# Steuerungsmodul.net
KiCad netlist of a schematic drawn in EAGLE
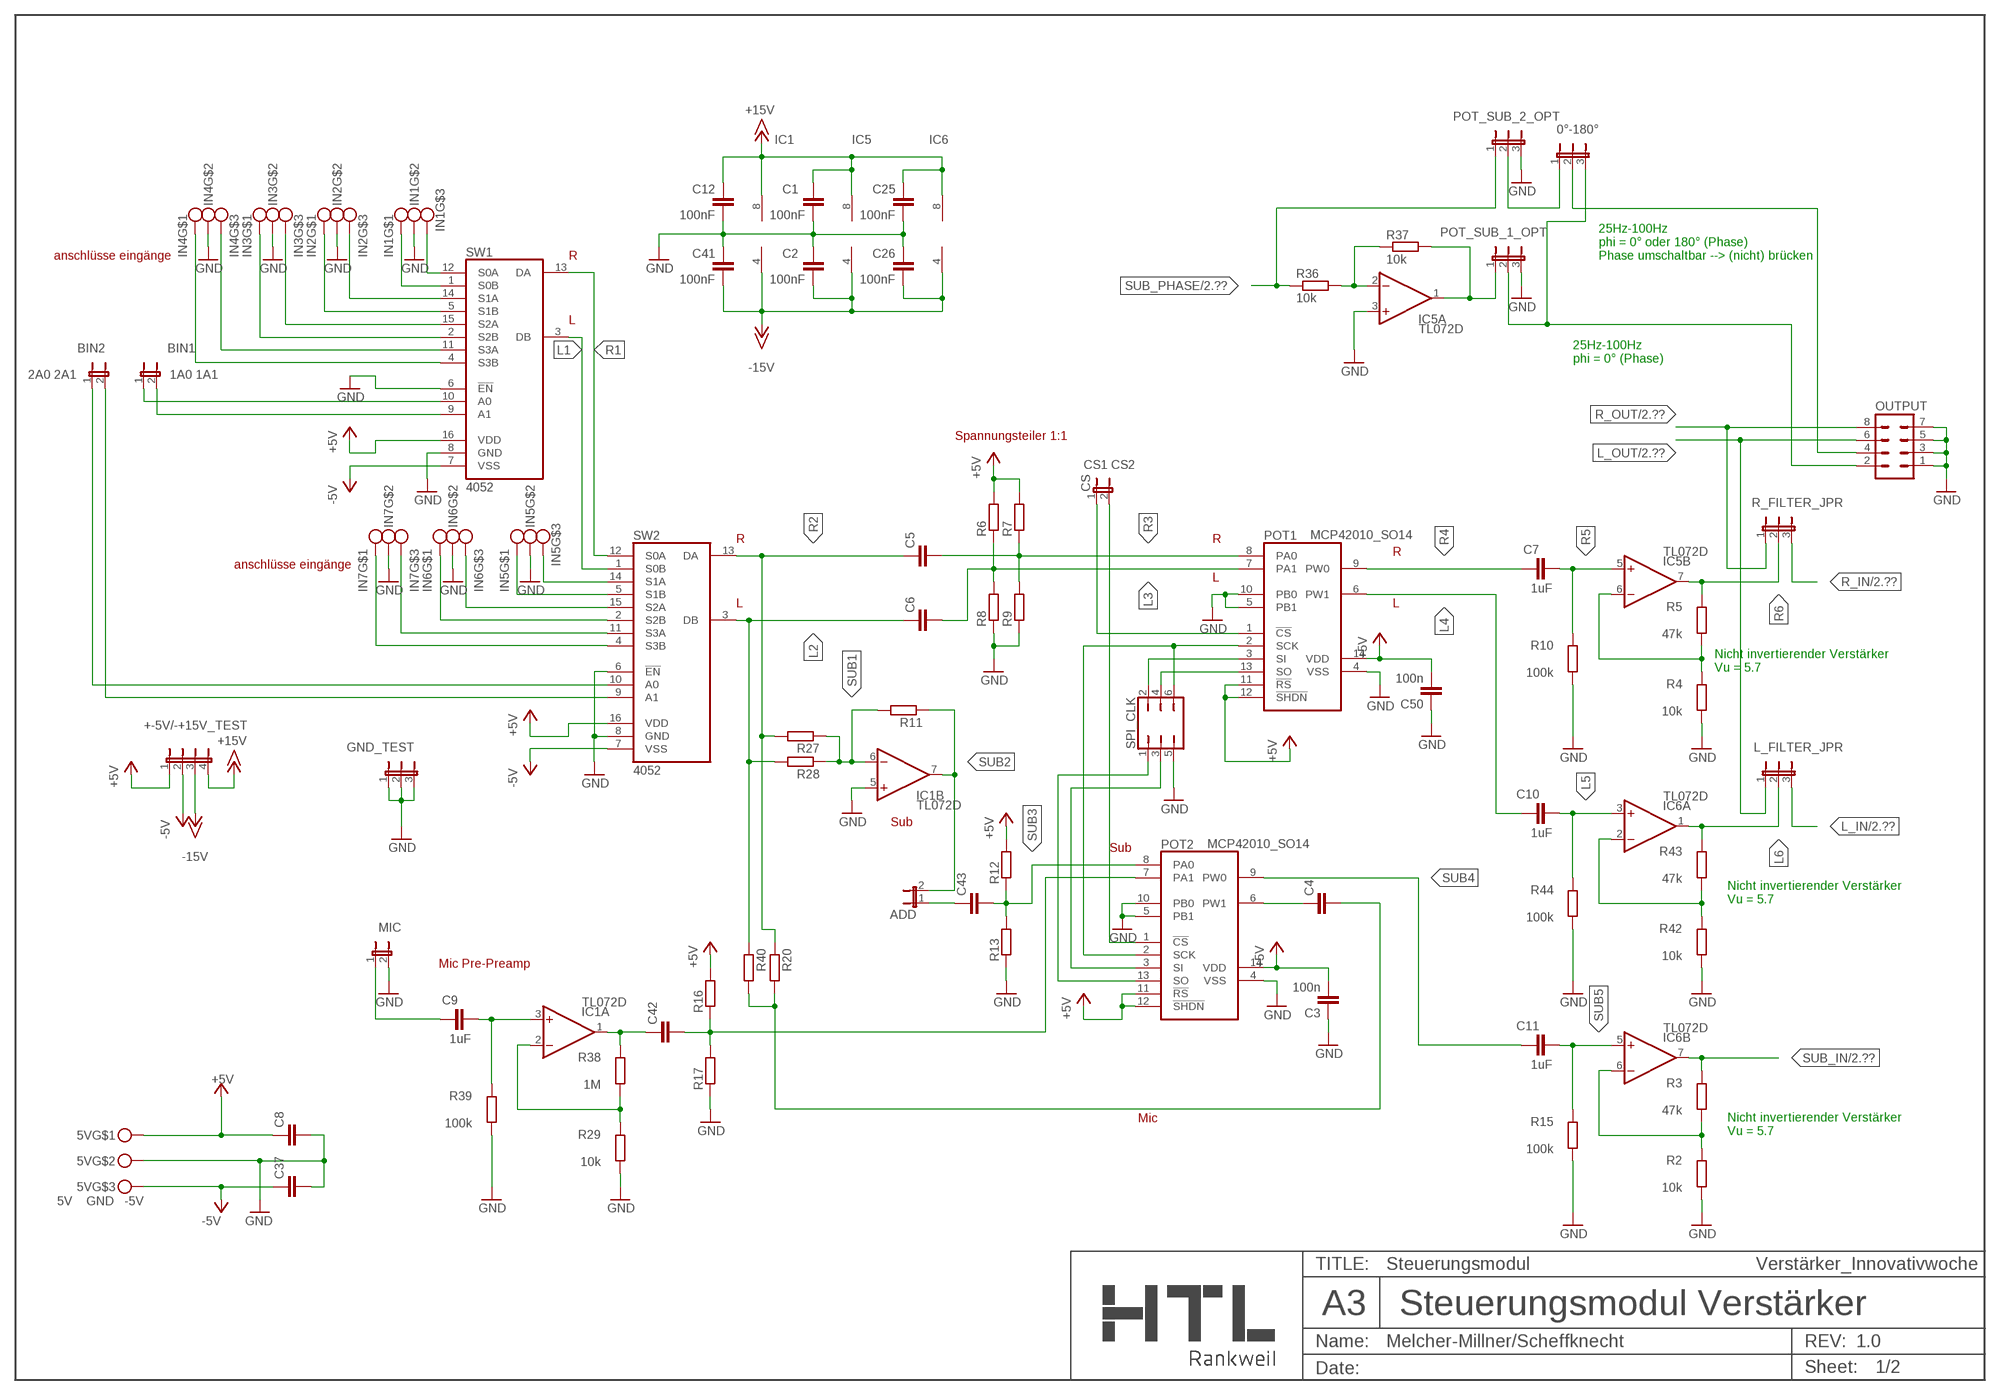
[diagram p0: schematic, sheet 1]
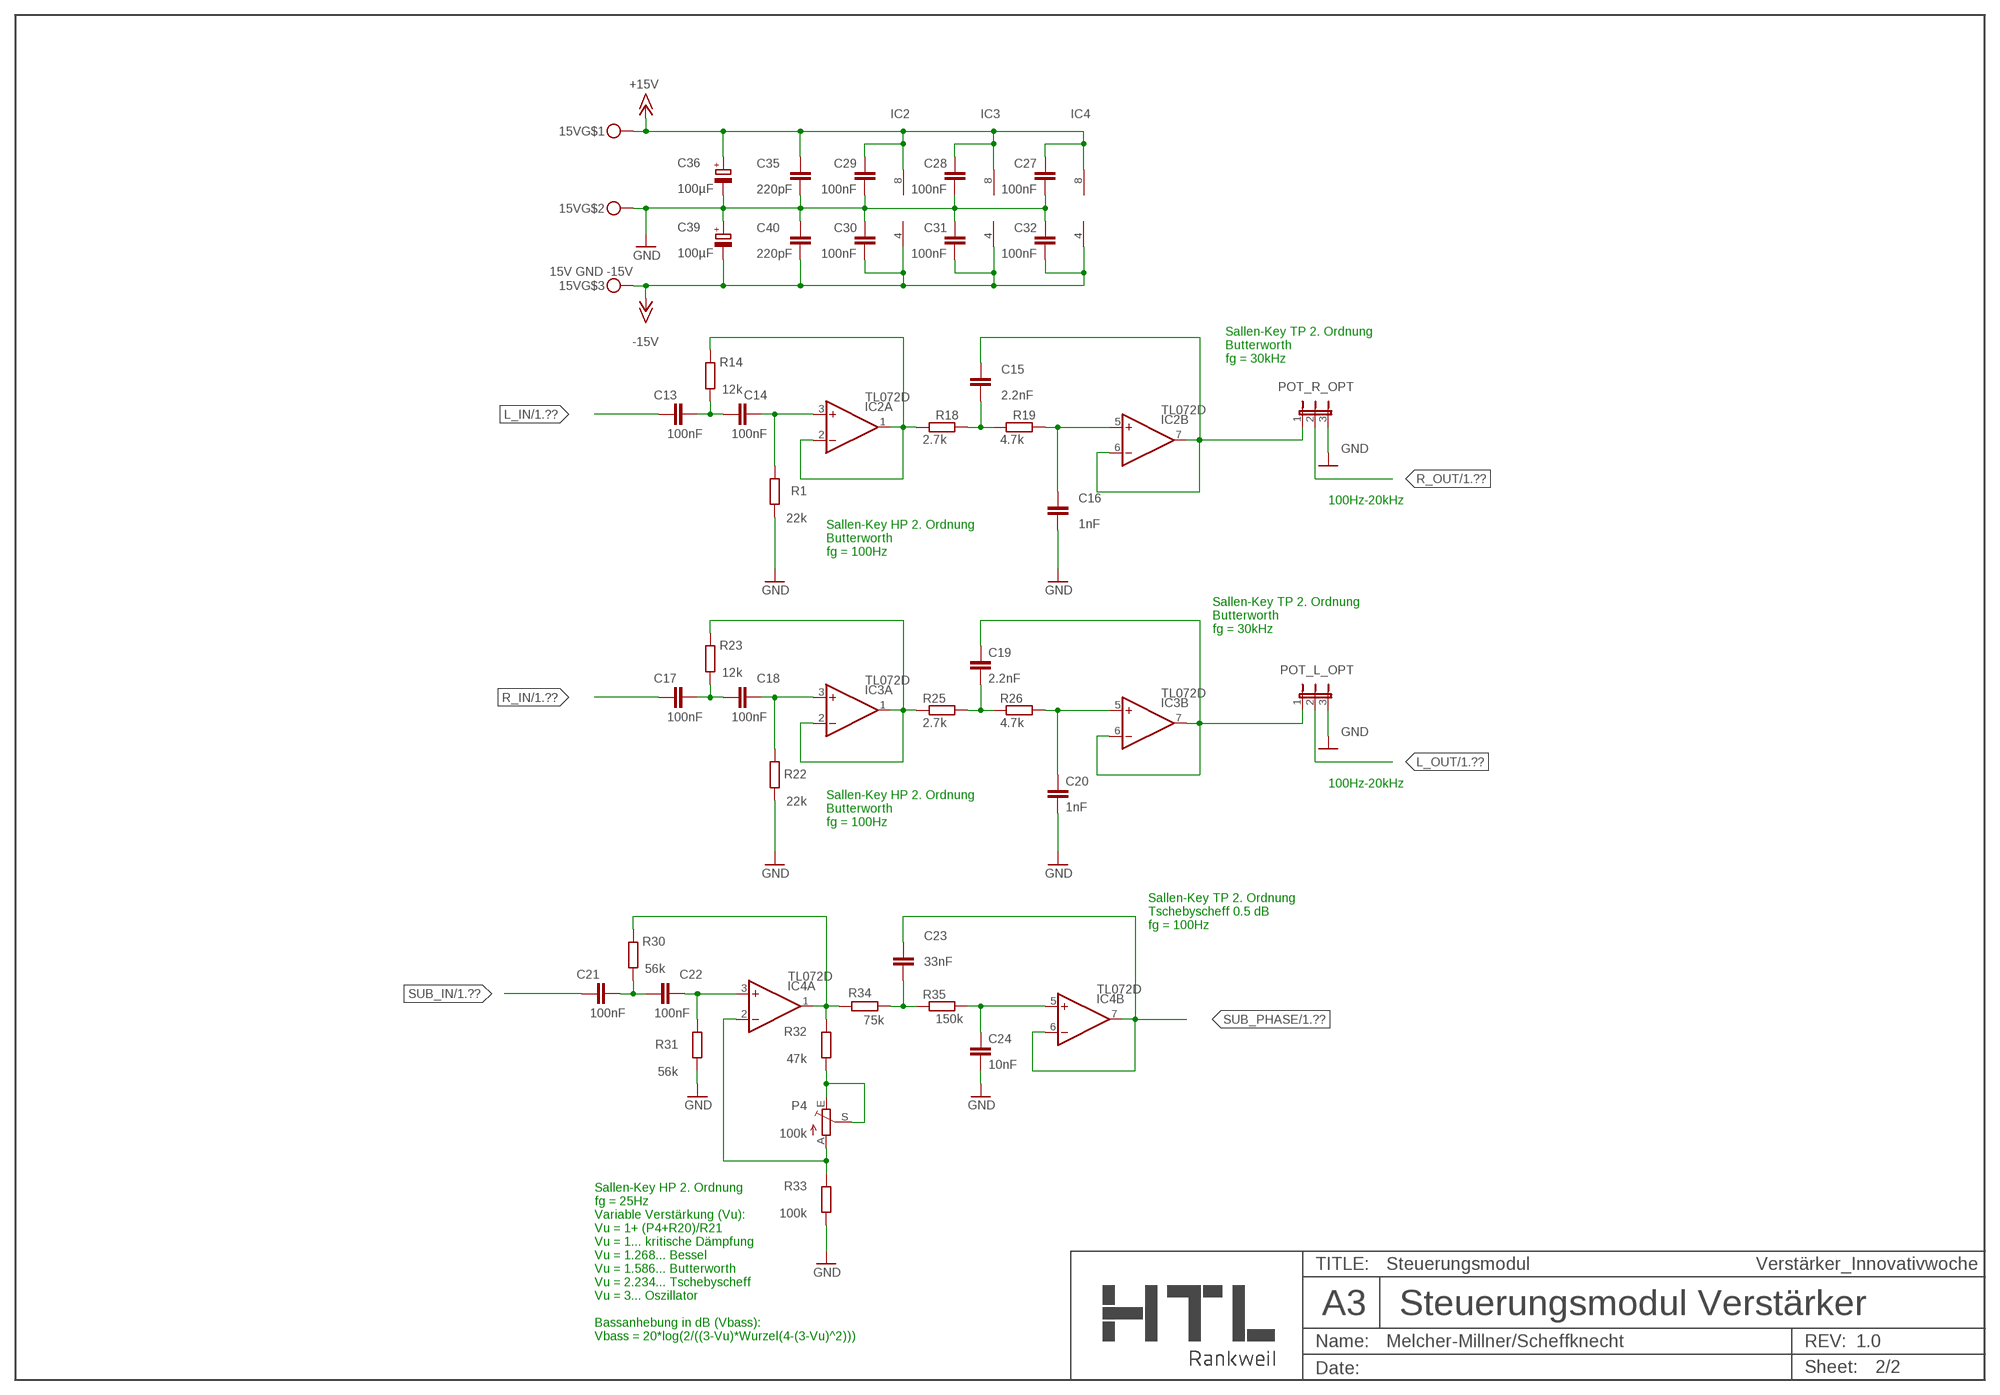
[diagram p1: schematic, sheet 2]

(export (version "E")
  (design (tool "Eeschema 10.0.6"))
  (components
    (comp (ref "15V")
      (value "15V GND -15V")
      (footprint "eagle-import:MKDS3_3_5,08")
      (libsource (lib "eagle-import") (part "MKDS3/3_5,08"))
    )
    (comp (ref "C13")
      (value "100nF")
      (footprint "eagle-import:C0805")
      (libsource (lib "eagle-import") (part "C-EUC0805"))
    )
    (comp (ref "C14")
      (value "100nF")
      (footprint "eagle-import:C0805")
      (libsource (lib "eagle-import") (part "C-EUC0805"))
    )
    (comp (ref "C15")
      (value "2.2nF")
      (footprint "eagle-import:C0805")
      (libsource (lib "eagle-import") (part "C-EUC0805"))
    )
    (comp (ref "C16")
      (value "1nF")
      (footprint "eagle-import:C0805")
      (libsource (lib "eagle-import") (part "C-EUC0805"))
    )
    (comp (ref "C17")
      (value "100nF")
      (footprint "eagle-import:C0805")
      (libsource (lib "eagle-import") (part "C-EUC0805"))
    )
    (comp (ref "C18")
      (value "100nF")
      (footprint "eagle-import:C0805")
      (libsource (lib "eagle-import") (part "C-EUC0805"))
    )
    (comp (ref "C19")
      (value "2.2nF")
      (footprint "eagle-import:C0805")
      (libsource (lib "eagle-import") (part "C-EUC0805"))
    )
    (comp (ref "C20")
      (value "1nF")
      (footprint "eagle-import:C0805")
      (libsource (lib "eagle-import") (part "C-EUC0805"))
    )
    (comp (ref "C21")
      (value "100nF")
      (footprint "eagle-import:C0805")
      (libsource (lib "eagle-import") (part "C-EUC0805"))
    )
    (comp (ref "C22")
      (value "100nF")
      (footprint "eagle-import:C0805")
      (libsource (lib "eagle-import") (part "C-EUC0805"))
    )
    (comp (ref "C23")
      (value "33nF")
      (footprint "eagle-import:C0805")
      (libsource (lib "eagle-import") (part "C-EUC0805"))
    )
    (comp (ref "C24")
      (value "10nF")
      (footprint "eagle-import:C0805")
      (libsource (lib "eagle-import") (part "C-EUC0805"))
    )
    (comp (ref "C27")
      (value "100nF")
      (footprint "eagle-import:C0805")
      (libsource (lib "eagle-import") (part "C-EUC0805"))
    )
    (comp (ref "C28")
      (value "100nF")
      (footprint "eagle-import:C0805")
      (libsource (lib "eagle-import") (part "C-EUC0805"))
    )
    (comp (ref "C29")
      (value "100nF")
      (footprint "eagle-import:C0805")
      (libsource (lib "eagle-import") (part "C-EUC0805"))
    )
    (comp (ref "C30")
      (value "100nF")
      (footprint "eagle-import:C0805")
      (libsource (lib "eagle-import") (part "C-EUC0805"))
    )
    (comp (ref "C31")
      (value "100nF")
      (footprint "eagle-import:C0805")
      (libsource (lib "eagle-import") (part "C-EUC0805"))
    )
    (comp (ref "C32")
      (value "100nF")
      (footprint "eagle-import:C0805")
      (libsource (lib "eagle-import") (part "C-EUC0805"))
    )
    (comp (ref "C35")
      (value "220pF")
      (footprint "eagle-import:C0805")
      (libsource (lib "eagle-import") (part "C-EUC0805"))
    )
    (comp (ref "C36")
      (value "100µF")
      (footprint "eagle-import:E2,5-6")
      (libsource (lib "eagle-import") (part "CPOL-EUE2.5-6"))
    )
    (comp (ref "C39")
      (value "100µF")
      (footprint "eagle-import:E2,5-6")
      (libsource (lib "eagle-import") (part "CPOL-EUE2.5-6"))
    )
    (comp (ref "C40")
      (value "220pF")
      (footprint "eagle-import:C0805")
      (libsource (lib "eagle-import") (part "C-EUC0805"))
    )
    (comp (ref "FRAME2")
      (value "HTL-A3-H")
      (footprint "eagle-import:HTL-LEER")
      (libsource (lib "eagle-import") (part "HTL-A3-H"))
    )
    (comp (ref "IC2")
      (value "TL072D")
      (footprint "eagle-import:SO08")
      (libsource (lib "eagle-import") (part "TL072D"))
    )
    (comp (ref "IC3")
      (value "TL072D")
      (footprint "eagle-import:SO08")
      (libsource (lib "eagle-import") (part "TL072D"))
    )
    (comp (ref "IC4")
      (value "TL072D")
      (footprint "eagle-import:SO08")
      (libsource (lib "eagle-import") (part "TL072D"))
    )
    (comp (ref "P4")
      (value "100k")
      (footprint "eagle-import:S64W")
      (libsource (lib "eagle-import") (part "TRIM_EU-S64W"))
    )
    (comp (ref "POT_L_OPT")
      (value "JMP3")
      (footprint "eagle-import:JMP3")
      (libsource (lib "eagle-import") (part "JMP3"))
    )
    (comp (ref "POT_R_OPT")
      (value "JMP3")
      (footprint "eagle-import:JMP3")
      (libsource (lib "eagle-import") (part "JMP3"))
    )
    (comp (ref "R1")
      (value "22k")
      (footprint "eagle-import:M0805")
      (libsource (lib "eagle-import") (part "R-EU_M0805"))
    )
    (comp (ref "R14")
      (value "12k")
      (footprint "eagle-import:M0805")
      (libsource (lib "eagle-import") (part "R-EU_M0805"))
    )
    (comp (ref "R18")
      (value "2.7k")
      (footprint "eagle-import:M0805")
      (libsource (lib "eagle-import") (part "R-EU_M0805"))
    )
    (comp (ref "R19")
      (value "4.7k")
      (footprint "eagle-import:M0805")
      (libsource (lib "eagle-import") (part "R-EU_M0805"))
    )
    (comp (ref "R22")
      (value "22k")
      (footprint "eagle-import:M0805")
      (libsource (lib "eagle-import") (part "R-EU_M0805"))
    )
    (comp (ref "R23")
      (value "12k")
      (footprint "eagle-import:M0805")
      (libsource (lib "eagle-import") (part "R-EU_M0805"))
    )
    (comp (ref "R25")
      (value "2.7k")
      (footprint "eagle-import:M0805")
      (libsource (lib "eagle-import") (part "R-EU_M0805"))
    )
    (comp (ref "R26")
      (value "4.7k")
      (footprint "eagle-import:M0805")
      (libsource (lib "eagle-import") (part "R-EU_M0805"))
    )
    (comp (ref "R30")
      (value "56k")
      (footprint "eagle-import:M0805")
      (libsource (lib "eagle-import") (part "R-EU_M0805"))
    )
    (comp (ref "R31")
      (value "56k")
      (footprint "eagle-import:M0805")
      (libsource (lib "eagle-import") (part "R-EU_M0805"))
    )
    (comp (ref "R32")
      (value "47k")
      (footprint "eagle-import:M0805")
      (libsource (lib "eagle-import") (part "R-EU_M0805"))
    )
    (comp (ref "R33")
      (value "100k")
      (footprint "eagle-import:M0805")
      (libsource (lib "eagle-import") (part "R-EU_M0805"))
    )
    (comp (ref "R34")
      (value "75k")
      (footprint "eagle-import:M0805")
      (libsource (lib "eagle-import") (part "R-EU_M0805"))
    )
    (comp (ref "R35")
      (value "150k")
      (footprint "eagle-import:M0805")
      (libsource (lib "eagle-import") (part "R-EU_M0805"))
    )
    (comp (ref "+-5V/-+15V_TEST")
      (value "JP4E")
      (footprint "eagle-import:JP4")
      (libsource (lib "eagle-import") (part "JP4E"))
    )
    (comp (ref "0°-180°")
      (value "JMP3")
      (footprint "eagle-import:JMP3")
      (libsource (lib "eagle-import") (part "JMP3"))
    )
    (comp (ref "5V")
      (value "5V GND -5V")
      (footprint "eagle-import:MKDS3_3_5,08")
      (libsource (lib "eagle-import") (part "MKDS3/3_5,08"))
    )
    (comp (ref "ADD")
      (value "JMP2")
      (footprint "eagle-import:JMP2")
      (libsource (lib "eagle-import") (part "JMP2"))
    )
    (comp (ref "BIN1")
      (value "1A0 1A1")
      (footprint "eagle-import:JMP2")
      (libsource (lib "eagle-import") (part "JMP2"))
    )
    (comp (ref "BIN2")
      (value "2A0 2A1")
      (footprint "eagle-import:JMP2")
      (fields (field (name "SPICEPREFIX") "B"))
      (libsource (lib "eagle-import") (part "JMP2"))
    )
    (comp (ref "C1")
      (value "100nF")
      (footprint "eagle-import:C0805")
      (libsource (lib "eagle-import") (part "C-EUC0805"))
    )
    (comp (ref "C2")
      (value "100nF")
      (footprint "eagle-import:C0805")
      (libsource (lib "eagle-import") (part "C-EUC0805"))
    )
    (comp (ref "C3")
      (value "100n")
      (footprint "eagle-import:C0805")
      (libsource (lib "eagle-import") (part "C-EUC0805"))
    )
    (comp (ref "C4")
      (value "C-EUC0805")
      (footprint "eagle-import:C0805")
      (libsource (lib "eagle-import") (part "C-EUC0805"))
    )
    (comp (ref "C5")
      (value "C-EUC0805")
      (footprint "eagle-import:C0805")
      (libsource (lib "eagle-import") (part "C-EUC0805"))
    )
    (comp (ref "C6")
      (value "C-EUC0805")
      (footprint "eagle-import:C0805")
      (libsource (lib "eagle-import") (part "C-EUC0805"))
    )
    (comp (ref "C7")
      (value "1uF")
      (footprint "eagle-import:C025-025X050")
      (libsource (lib "eagle-import") (part "resistor_C-EU025-025X050"))
    )
    (comp (ref "C8")
      (value "C-EUC0805")
      (footprint "eagle-import:C0805")
      (libsource (lib "eagle-import") (part "C-EUC0805"))
    )
    (comp (ref "C9")
      (value "1uF")
      (footprint "eagle-import:C025-025X050")
      (libsource (lib "eagle-import") (part "resistor_C-EU025-025X050"))
    )
    (comp (ref "C10")
      (value "1uF")
      (footprint "eagle-import:C025-025X050")
      (libsource (lib "eagle-import") (part "resistor_C-EU025-025X050"))
    )
    (comp (ref "C11")
      (value "1uF")
      (footprint "eagle-import:C025-025X050")
      (libsource (lib "eagle-import") (part "resistor_C-EU025-025X050"))
    )
    (comp (ref "C12")
      (value "100nF")
      (footprint "eagle-import:C0805")
      (libsource (lib "eagle-import") (part "C-EUC0805"))
    )
    (comp (ref "C25")
      (value "100nF")
      (footprint "eagle-import:C0805")
      (libsource (lib "eagle-import") (part "C-EUC0805"))
    )
    (comp (ref "C26")
      (value "100nF")
      (footprint "eagle-import:C0805")
      (libsource (lib "eagle-import") (part "C-EUC0805"))
    )
    (comp (ref "C37")
      (value "C-EUC0805")
      (footprint "eagle-import:C0805")
      (libsource (lib "eagle-import") (part "C-EUC0805"))
    )
    (comp (ref "C41")
      (value "100nF")
      (footprint "eagle-import:C0805")
      (libsource (lib "eagle-import") (part "C-EUC0805"))
    )
    (comp (ref "C42")
      (value "C-EUC0805")
      (footprint "eagle-import:C0805")
      (libsource (lib "eagle-import") (part "C-EUC0805"))
    )
    (comp (ref "C43")
      (value "C-EUC0805")
      (footprint "eagle-import:C0805")
      (libsource (lib "eagle-import") (part "C-EUC0805"))
    )
    (comp (ref "C50")
      (value "100n")
      (footprint "eagle-import:C0805")
      (libsource (lib "eagle-import") (part "C-EUC0805"))
    )
    (comp (ref "CS")
      (value "CS1 CS2")
      (footprint "eagle-import:JMP2")
      (libsource (lib "eagle-import") (part "JMP2"))
    )
    (comp (ref "FRAME1")
      (value "HTL-A3-H")
      (footprint "eagle-import:HTL-LEER")
      (libsource (lib "eagle-import") (part "HTL-A3-H"))
    )
    (comp (ref "GND_TEST")
      (value "JMP3")
      (footprint "eagle-import:JMP3")
      (libsource (lib "eagle-import") (part "JMP3"))
    )
    (comp (ref "IC1")
      (value "TL072D")
      (footprint "eagle-import:SO08")
      (libsource (lib "eagle-import") (part "TL072D"))
    )
    (comp (ref "IC5")
      (value "TL072D")
      (footprint "eagle-import:SO08")
      (libsource (lib "eagle-import") (part "TL072D"))
    )
    (comp (ref "IC6")
      (value "TL072D")
      (footprint "eagle-import:SO08")
      (libsource (lib "eagle-import") (part "TL072D"))
    )
    (comp (ref "IN1")
      (value "MKDS3/3_5,08")
      (footprint "eagle-import:MKDS3_3_5,08")
      (libsource (lib "eagle-import") (part "MKDS3/3_5,08"))
    )
    (comp (ref "IN2")
      (value "MKDS3/3_5,08")
      (footprint "eagle-import:MKDS3_3_5,08")
      (libsource (lib "eagle-import") (part "MKDS3/3_5,08"))
    )
    (comp (ref "IN3")
      (value "MKDS3/3_5,08")
      (footprint "eagle-import:MKDS3_3_5,08")
      (libsource (lib "eagle-import") (part "MKDS3/3_5,08"))
    )
    (comp (ref "IN4")
      (value "MKDS3/3_5,08")
      (footprint "eagle-import:MKDS3_3_5,08")
      (libsource (lib "eagle-import") (part "MKDS3/3_5,08"))
    )
    (comp (ref "IN5")
      (value "MKDS3/3_5,08")
      (footprint "eagle-import:MKDS3_3_5,08")
      (libsource (lib "eagle-import") (part "MKDS3/3_5,08"))
    )
    (comp (ref "IN6")
      (value "MKDS3/3_5,08")
      (footprint "eagle-import:MKDS3_3_5,08")
      (libsource (lib "eagle-import") (part "MKDS3/3_5,08"))
    )
    (comp (ref "IN7")
      (value "MKDS3/3_5,08")
      (footprint "eagle-import:MKDS3_3_5,08")
      (libsource (lib "eagle-import") (part "MKDS3/3_5,08"))
    )
    (comp (ref "L_FILTER_JPR")
      (value "JMP3")
      (footprint "eagle-import:JMP3")
      (libsource (lib "eagle-import") (part "JMP3"))
    )
    (comp (ref "MIC")
      (value "JMP2")
      (footprint "eagle-import:JMP2")
      (libsource (lib "eagle-import") (part "JMP2"))
    )
    (comp (ref "OUTPUT")
      (value "MA04-2")
      (footprint "eagle-import:MA04-2")
      (libsource (lib "eagle-import") (part "MA04-2"))
    )
    (comp (ref "POT1")
      (value "MCP42010_SO14")
      (footprint "eagle-import:SO14")
      (libsource (lib "eagle-import") (part "MCP42010_SO14"))
    )
    (comp (ref "POT2")
      (value "MCP42010_SO14")
      (footprint "eagle-import:SO14")
      (libsource (lib "eagle-import") (part "MCP42010_SO14"))
    )
    (comp (ref "POT_SUB_1_OPT")
      (value "JMP3")
      (footprint "eagle-import:JMP3")
      (libsource (lib "eagle-import") (part "JMP3"))
    )
    (comp (ref "POT_SUB_2_OPT")
      (value "JMP3")
      (footprint "eagle-import:JMP3")
      (libsource (lib "eagle-import") (part "JMP3"))
    )
    (comp (ref "R2")
      (value "10k")
      (footprint "eagle-import:M0805")
      (libsource (lib "eagle-import") (part "R-EU_M0805"))
    )
    (comp (ref "R3")
      (value "47k")
      (footprint "eagle-import:M0805")
      (libsource (lib "eagle-import") (part "R-EU_M0805"))
    )
    (comp (ref "R4")
      (value "10k")
      (footprint "eagle-import:M0805")
      (libsource (lib "eagle-import") (part "R-EU_M0805"))
    )
    (comp (ref "R5")
      (value "47k")
      (footprint "eagle-import:M0805")
      (libsource (lib "eagle-import") (part "R-EU_M0805"))
    )
    (comp (ref "R6")
      (value "R-EU_M0805")
      (footprint "eagle-import:M0805")
      (libsource (lib "eagle-import") (part "R-EU_M0805"))
    )
    (comp (ref "R7")
      (value "R-EU_M0805")
      (footprint "eagle-import:M0805")
      (libsource (lib "eagle-import") (part "R-EU_M0805"))
    )
    (comp (ref "R8")
      (value "R-EU_M0805")
      (footprint "eagle-import:M0805")
      (libsource (lib "eagle-import") (part "R-EU_M0805"))
    )
    (comp (ref "R9")
      (value "R-EU_M0805")
      (footprint "eagle-import:M0805")
      (libsource (lib "eagle-import") (part "R-EU_M0805"))
    )
    (comp (ref "R10")
      (value "100k")
      (footprint "eagle-import:M0805")
      (libsource (lib "eagle-import") (part "R-EU_M0805"))
    )
    (comp (ref "R11")
      (value "R-EU_M0805")
      (footprint "eagle-import:M0805")
      (libsource (lib "eagle-import") (part "R-EU_M0805"))
    )
    (comp (ref "R12")
      (value "R-EU_M0805")
      (footprint "eagle-import:M0805")
      (libsource (lib "eagle-import") (part "R-EU_M0805"))
    )
    (comp (ref "R13")
      (value "R-EU_M0805")
      (footprint "eagle-import:M0805")
      (libsource (lib "eagle-import") (part "R-EU_M0805"))
    )
    (comp (ref "R15")
      (value "100k")
      (footprint "eagle-import:M0805")
      (libsource (lib "eagle-import") (part "R-EU_M0805"))
    )
    (comp (ref "R16")
      (value "R-EU_M0805")
      (footprint "eagle-import:M0805")
      (libsource (lib "eagle-import") (part "R-EU_M0805"))
    )
    (comp (ref "R17")
      (value "R-EU_M0805")
      (footprint "eagle-import:M0805")
      (libsource (lib "eagle-import") (part "R-EU_M0805"))
    )
    (comp (ref "R20")
      (value "R-EU_M0805")
      (footprint "eagle-import:M0805")
      (libsource (lib "eagle-import") (part "R-EU_M0805"))
    )
    (comp (ref "R27")
      (value "R-EU_M0805")
      (footprint "eagle-import:M0805")
      (libsource (lib "eagle-import") (part "R-EU_M0805"))
    )
    (comp (ref "R28")
      (value "R-EU_M0805")
      (footprint "eagle-import:M0805")
      (libsource (lib "eagle-import") (part "R-EU_M0805"))
    )
    (comp (ref "R29")
      (value "10k")
      (footprint "eagle-import:M0805")
      (libsource (lib "eagle-import") (part "R-EU_M0805"))
    )
    (comp (ref "R36")
      (value "10k")
      (footprint "eagle-import:M0805")
      (libsource (lib "eagle-import") (part "R-EU_M0805"))
    )
    (comp (ref "R37")
      (value "10k")
      (footprint "eagle-import:M0805")
      (libsource (lib "eagle-import") (part "R-EU_M0805"))
    )
    (comp (ref "R38")
      (value "1M")
      (footprint "eagle-import:M0805")
      (libsource (lib "eagle-import") (part "R-EU_M0805"))
    )
    (comp (ref "R39")
      (value "100k")
      (footprint "eagle-import:M0805")
      (libsource (lib "eagle-import") (part "R-EU_M0805"))
    )
    (comp (ref "R40")
      (value "R-EU_M0805")
      (footprint "eagle-import:M0805")
      (libsource (lib "eagle-import") (part "R-EU_M0805"))
    )
    (comp (ref "R42")
      (value "10k")
      (footprint "eagle-import:M0805")
      (libsource (lib "eagle-import") (part "R-EU_M0805"))
    )
    (comp (ref "R43")
      (value "47k")
      (footprint "eagle-import:M0805")
      (libsource (lib "eagle-import") (part "R-EU_M0805"))
    )
    (comp (ref "R44")
      (value "100k")
      (footprint "eagle-import:M0805")
      (libsource (lib "eagle-import") (part "R-EU_M0805"))
    )
    (comp (ref "R_FILTER_JPR")
      (value "JMP3")
      (footprint "eagle-import:JMP3")
      (libsource (lib "eagle-import") (part "JMP3"))
    )
    (comp (ref "SPI_CLK")
      (value "JP3Q")
      (footprint "eagle-import:JP3Q")
      (libsource (lib "eagle-import") (part "JP3Q"))
    )
    (comp (ref "SW1")
      (value "4052")
      (footprint "eagle-import:SO-16")
      (libsource (lib "eagle-import") (part "5042_SO16_NEU"))
    )
    (comp (ref "SW2")
      (value "4052")
      (footprint "eagle-import:SO-16")
      (libsource (lib "eagle-import") (part "5042_SO16_NEU"))
    )
  )
  (nets
    (net (code "1") (name "+5V") (class "Default")
      (node (ref "+-5V/-+15V_TEST") (pin "1") (pinfunction "1_1") (pintype "passive"))
      (node (ref "5V") (pin "P$1") (pinfunction "KL_P$1") (pintype "passive"))
      (node (ref "C3") (pin "2") (pinfunction "2_2") (pintype "passive"))
      (node (ref "C50") (pin "2") (pinfunction "2_2") (pintype "passive"))
      (node (ref "C8") (pin "1") (pinfunction "1_1") (pintype "passive"))
      (node (ref "POT1") (pin "11") (pinfunction "~{RS}_11") (pintype "bidirectional"))
      (node (ref "POT1") (pin "12") (pinfunction "~{SHDN}_12") (pintype "bidirectional"))
      (node (ref "POT1") (pin "14") (pinfunction "VDD_14") (pintype "input"))
      (node (ref "POT2") (pin "11") (pinfunction "~{RS}_11") (pintype "bidirectional"))
      (node (ref "POT2") (pin "12") (pinfunction "~{SHDN}_12") (pintype "bidirectional"))
      (node (ref "POT2") (pin "14") (pinfunction "VDD_14") (pintype "input"))
      (node (ref "R12") (pin "2") (pinfunction "2_2") (pintype "passive"))
      (node (ref "R16") (pin "2") (pinfunction "2_2") (pintype "passive"))
      (node (ref "R6") (pin "2") (pinfunction "2_2") (pintype "passive"))
      (node (ref "R7") (pin "2") (pinfunction "2_2") (pintype "passive"))
      (node (ref "SW1") (pin "16") (pinfunction "VDD_16") (pintype "bidirectional"))
      (node (ref "SW2") (pin "16") (pinfunction "VDD_16") (pintype "bidirectional"))
    )
    (net (code "2") (name "+15V") (class "Default")
      (node (ref "+-5V/-+15V_TEST") (pin "4") (pinfunction "4_4") (pintype "passive"))
      (node (ref "15V") (pin "P$1") (pinfunction "KL_P$1") (pintype "passive"))
      (node (ref "C1") (pin "1") (pinfunction "1_1") (pintype "passive"))
      (node (ref "C12") (pin "1") (pinfunction "1_1") (pintype "passive"))
      (node (ref "C25") (pin "1") (pinfunction "1_1") (pintype "passive"))
      (node (ref "C27") (pin "1") (pinfunction "1_1") (pintype "passive"))
      (node (ref "C28") (pin "1") (pinfunction "1_1") (pintype "passive"))
      (node (ref "C29") (pin "1") (pinfunction "1_1") (pintype "passive"))
      (node (ref "C35") (pin "1") (pinfunction "1_1") (pintype "passive"))
      (node (ref "C36") (pin "+") (pinfunction "+_+") (pintype "passive"))
      (node (ref "IC1") (pin "8") (pinfunction "V+_8") (pintype "power_in"))
      (node (ref "IC2") (pin "8") (pinfunction "V+_8") (pintype "power_in"))
      (node (ref "IC3") (pin "8") (pinfunction "V+_8") (pintype "power_in"))
      (node (ref "IC4") (pin "8") (pinfunction "V+_8") (pintype "power_in"))
      (node (ref "IC5") (pin "8") (pinfunction "V+_8") (pintype "power_in"))
      (node (ref "IC6") (pin "8") (pinfunction "V+_8") (pintype "power_in"))
    )
    (net (code "3") (name "-5V") (class "Default")
      (node (ref "+-5V/-+15V_TEST") (pin "2") (pinfunction "2_2") (pintype "passive"))
      (node (ref "5V") (pin "P$3") (pinfunction "KL_P$3") (pintype "passive"))
      (node (ref "C37") (pin "1") (pinfunction "1_1") (pintype "passive"))
      (node (ref "SW1") (pin "7") (pinfunction "VSS_7") (pintype "bidirectional"))
      (node (ref "SW2") (pin "7") (pinfunction "VSS_7") (pintype "bidirectional"))
    )
    (net (code "4") (name "-15V") (class "Default")
      (node (ref "+-5V/-+15V_TEST") (pin "3") (pinfunction "3_3") (pintype "passive"))
      (node (ref "15V") (pin "P$3") (pinfunction "KL_P$3") (pintype "passive"))
      (node (ref "C2") (pin "2") (pinfunction "2_2") (pintype "passive"))
      (node (ref "C26") (pin "2") (pinfunction "2_2") (pintype "passive"))
      (node (ref "C30") (pin "2") (pinfunction "2_2") (pintype "passive"))
      (node (ref "C31") (pin "2") (pinfunction "2_2") (pintype "passive"))
      (node (ref "C32") (pin "2") (pinfunction "2_2") (pintype "passive"))
      (node (ref "C39") (pin "-") (pinfunction "-_-") (pintype "passive"))
      (node (ref "C40") (pin "2") (pinfunction "2_2") (pintype "passive"))
      (node (ref "C41") (pin "2") (pinfunction "2_2") (pintype "passive"))
      (node (ref "IC1") (pin "4") (pinfunction "V-_4") (pintype "power_in"))
      (node (ref "IC2") (pin "4") (pinfunction "V-_4") (pintype "power_in"))
      (node (ref "IC3") (pin "4") (pinfunction "V-_4") (pintype "power_in"))
      (node (ref "IC4") (pin "4") (pinfunction "V-_4") (pintype "power_in"))
      (node (ref "IC5") (pin "4") (pinfunction "V-_4") (pintype "power_in"))
      (node (ref "IC6") (pin "4") (pinfunction "V-_4") (pintype "power_in"))
    )
    (net (code "5") (name "GND") (class "Default")
      (node (ref "15V") (pin "P$2") (pinfunction "KL_P$2") (pintype "passive"))
      (node (ref "5V") (pin "P$2") (pinfunction "KL_P$2") (pintype "passive"))
      (node (ref "C1") (pin "2") (pinfunction "2_2") (pintype "passive"))
      (node (ref "C12") (pin "2") (pinfunction "2_2") (pintype "passive"))
      (node (ref "C16") (pin "2") (pinfunction "2_2") (pintype "passive"))
      (node (ref "C2") (pin "1") (pinfunction "1_1") (pintype "passive"))
      (node (ref "C20") (pin "2") (pinfunction "2_2") (pintype "passive"))
      (node (ref "C24") (pin "2") (pinfunction "2_2") (pintype "passive"))
      (node (ref "C25") (pin "2") (pinfunction "2_2") (pintype "passive"))
      (node (ref "C26") (pin "1") (pinfunction "1_1") (pintype "passive"))
      (node (ref "C27") (pin "2") (pinfunction "2_2") (pintype "passive"))
      (node (ref "C28") (pin "2") (pinfunction "2_2") (pintype "passive"))
      (node (ref "C29") (pin "2") (pinfunction "2_2") (pintype "passive"))
      (node (ref "C3") (pin "1") (pinfunction "1_1") (pintype "passive"))
      (node (ref "C30") (pin "1") (pinfunction "1_1") (pintype "passive"))
      (node (ref "C31") (pin "1") (pinfunction "1_1") (pintype "passive"))
      (node (ref "C32") (pin "1") (pinfunction "1_1") (pintype "passive"))
      (node (ref "C35") (pin "2") (pinfunction "2_2") (pintype "passive"))
      (node (ref "C36") (pin "-") (pinfunction "-_-") (pintype "passive"))
      (node (ref "C37") (pin "2") (pinfunction "2_2") (pintype "passive"))
      (node (ref "C39") (pin "+") (pinfunction "+_+") (pintype "passive"))
      (node (ref "C40") (pin "1") (pinfunction "1_1") (pintype "passive"))
      (node (ref "C41") (pin "1") (pinfunction "1_1") (pintype "passive"))
      (node (ref "C50") (pin "1") (pinfunction "1_1") (pintype "passive"))
      (node (ref "C8") (pin "2") (pinfunction "2_2") (pintype "passive"))
      (node (ref "GND_TEST") (pin "1") (pinfunction "1_1") (pintype "passive"))
      (node (ref "GND_TEST") (pin "2") (pinfunction "2_2") (pintype "passive"))
      (node (ref "GND_TEST") (pin "3") (pinfunction "3_3") (pintype "passive"))
      (node (ref "IC1") (pin "5") (pinfunction "+IN_5") (pintype "input"))
      (node (ref "IC5") (pin "3") (pinfunction "+IN_3") (pintype "input"))
      (node (ref "IN1") (pin "P$2") (pinfunction "KL_P$2") (pintype "passive"))
      (node (ref "IN2") (pin "P$2") (pinfunction "KL_P$2") (pintype "passive"))
      (node (ref "IN3") (pin "P$2") (pinfunction "KL_P$2") (pintype "passive"))
      (node (ref "IN4") (pin "P$2") (pinfunction "KL_P$2") (pintype "passive"))
      (node (ref "IN5") (pin "P$2") (pinfunction "KL_P$2") (pintype "passive"))
      (node (ref "IN6") (pin "P$2") (pinfunction "KL_P$2") (pintype "passive"))
      (node (ref "IN7") (pin "P$2") (pinfunction "KL_P$2") (pintype "passive"))
      (node (ref "MIC") (pin "2") (pinfunction "2_2") (pintype "passive"))
      (node (ref "OUTPUT") (pin "1") (pinfunction "1_1") (pintype "passive"))
      (node (ref "OUTPUT") (pin "3") (pinfunction "3_3") (pintype "passive"))
      (node (ref "OUTPUT") (pin "5") (pinfunction "5_5") (pintype "passive"))
      (node (ref "OUTPUT") (pin "7") (pinfunction "7_7") (pintype "passive"))
      (node (ref "POT1") (pin "10") (pinfunction "PB0_10") (pintype "bidirectional"))
      (node (ref "POT1") (pin "4") (pinfunction "VSS_4") (pintype "input"))
      (node (ref "POT1") (pin "5") (pinfunction "PB1_5") (pintype "bidirectional"))
      (node (ref "POT2") (pin "10") (pinfunction "PB0_10") (pintype "bidirectional"))
      (node (ref "POT2") (pin "4") (pinfunction "VSS_4") (pintype "input"))
      (node (ref "POT2") (pin "5") (pinfunction "PB1_5") (pintype "bidirectional"))
      (node (ref "POT_L_OPT") (pin "3") (pinfunction "3_3") (pintype "passive"))
      (node (ref "POT_R_OPT") (pin "3") (pinfunction "3_3") (pintype "passive"))
      (node (ref "POT_SUB_1_OPT") (pin "3") (pinfunction "3_3") (pintype "passive"))
      (node (ref "POT_SUB_2_OPT") (pin "3") (pinfunction "3_3") (pintype "passive"))
      (node (ref "R1") (pin "1") (pinfunction "1_1") (pintype "passive"))
      (node (ref "R10") (pin "1") (pinfunction "1_1") (pintype "passive"))
      (node (ref "R13") (pin "1") (pinfunction "1_1") (pintype "passive"))
      (node (ref "R15") (pin "1") (pinfunction "1_1") (pintype "passive"))
      (node (ref "R17") (pin "1") (pinfunction "1_1") (pintype "passive"))
      (node (ref "R2") (pin "1") (pinfunction "1_1") (pintype "passive"))
      (node (ref "R22") (pin "1") (pinfunction "1_1") (pintype "passive"))
      (node (ref "R29") (pin "1") (pinfunction "1_1") (pintype "passive"))
      (node (ref "R31") (pin "1") (pinfunction "1_1") (pintype "passive"))
      (node (ref "R33") (pin "1") (pinfunction "1_1") (pintype "passive"))
      (node (ref "R39") (pin "1") (pinfunction "1_1") (pintype "passive"))
      (node (ref "R4") (pin "1") (pinfunction "1_1") (pintype "passive"))
      (node (ref "R42") (pin "1") (pinfunction "1_1") (pintype "passive"))
      (node (ref "R44") (pin "1") (pinfunction "1_1") (pintype "passive"))
      (node (ref "R8") (pin "1") (pinfunction "1_1") (pintype "passive"))
      (node (ref "R9") (pin "1") (pinfunction "1_1") (pintype "passive"))
      (node (ref "SPI_CLK") (pin "5") (pinfunction "5_5") (pintype "passive"))
      (node (ref "SW1") (pin "6") (pinfunction "~{EN}_6") (pintype "input"))
      (node (ref "SW1") (pin "8") (pinfunction "GND_8") (pintype "bidirectional"))
      (node (ref "SW2") (pin "6") (pinfunction "~{EN}_6") (pintype "input"))
      (node (ref "SW2") (pin "8") (pinfunction "GND_8") (pintype "bidirectional"))
    )
    (net (code "6") (name "L1") (class "Default")
      (node (ref "SW1") (pin "3") (pinfunction "DB_3") (pintype "bidirectional"))
      (node (ref "SW2") (pin "1") (pinfunction "S0B_1") (pintype "bidirectional"))
    )
    (net (code "7") (name "L2") (class "Default")
      (node (ref "C6") (pin "1") (pinfunction "1_1") (pintype "passive"))
      (node (ref "R28") (pin "2") (pinfunction "2_2") (pintype "passive"))
      (node (ref "R40") (pin "1") (pinfunction "1_1") (pintype "passive"))
      (node (ref "SW2") (pin "3") (pinfunction "DB_3") (pintype "bidirectional"))
    )
    (net (code "8") (name "L3") (class "Default")
      (node (ref "C6") (pin "2") (pinfunction "2_2") (pintype "passive"))
      (node (ref "POT1") (pin "7") (pinfunction "PA1_7") (pintype "bidirectional"))
      (node (ref "R6") (pin "1") (pinfunction "1_1") (pintype "passive"))
      (node (ref "R8") (pin "2") (pinfunction "2_2") (pintype "passive"))
    )
    (net (code "9") (name "L4") (class "Default")
      (node (ref "C10") (pin "1") (pinfunction "1_1") (pintype "passive"))
      (node (ref "POT1") (pin "6") (pinfunction "PW1_6") (pintype "bidirectional"))
    )
    (net (code "10") (name "L5") (class "Default")
      (node (ref "C10") (pin "2") (pinfunction "2_2") (pintype "passive"))
      (node (ref "IC6") (pin "3") (pinfunction "+IN_3") (pintype "input"))
      (node (ref "R44") (pin "2") (pinfunction "2_2") (pintype "passive"))
    )
    (net (code "11") (name "L6") (class "Default")
      (node (ref "IC6") (pin "1") (pinfunction "OUT_1") (pintype "output"))
      (node (ref "L_FILTER_JPR") (pin "2") (pinfunction "2_2") (pintype "passive"))
      (node (ref "R43") (pin "2") (pinfunction "2_2") (pintype "passive"))
    )
    (net (code "12") (name "L_IN") (class "Default")
      (node (ref "C13") (pin "1") (pinfunction "1_1") (pintype "passive"))
      (node (ref "L_FILTER_JPR") (pin "3") (pinfunction "3_3") (pintype "passive"))
    )
    (net (code "13") (name "L_OUT") (class "Default")
      (node (ref "L_FILTER_JPR") (pin "1") (pinfunction "1_1") (pintype "passive"))
      (node (ref "OUTPUT") (pin "6") (pinfunction "6_6") (pintype "passive"))
      (node (ref "POT_L_OPT") (pin "2") (pinfunction "2_2") (pintype "passive"))
    )
    (net (code "14") (name "Net-(0°-180°-Pad1)") (class "Default")
      (node (ref "0°-180°") (pin "1") (pinfunction "1_1") (pintype "passive"))
      (node (ref "POT_SUB_2_OPT") (pin "2") (pinfunction "2_2") (pintype "passive"))
    )
    (net (code "15") (name "Net-(0°-180°-Pad2)") (class "Default")
      (node (ref "0°-180°") (pin "2") (pinfunction "2_2") (pintype "passive"))
      (node (ref "OUTPUT") (pin "4") (pinfunction "4_4") (pintype "passive"))
    )
    (net (code "16") (name "Net-(0°-180°-Pad3)") (class "Default")
      (node (ref "0°-180°") (pin "3") (pinfunction "3_3") (pintype "passive"))
      (node (ref "OUTPUT") (pin "2") (pinfunction "2_2") (pintype "passive"))
      (node (ref "POT_SUB_1_OPT") (pin "2") (pinfunction "2_2") (pintype "passive"))
    )
    (net (code "17") (name "Net-(ADD-Pad1)") (class "Default")
      (node (ref "ADD") (pin "1") (pinfunction "1_1") (pintype "passive"))
      (node (ref "C43") (pin "1") (pinfunction "1_1") (pintype "passive"))
    )
    (net (code "18") (name "Net-(C4-Pad2)") (class "Default")
      (node (ref "C4") (pin "2") (pinfunction "2_2") (pintype "passive"))
      (node (ref "R20") (pin "2") (pinfunction "2_2") (pintype "passive"))
      (node (ref "R40") (pin "2") (pinfunction "2_2") (pintype "passive"))
    )
    (net (code "19") (name "Net-(C9-Pad1)") (class "Default")
      (node (ref "C9") (pin "1") (pinfunction "1_1") (pintype "passive"))
      (node (ref "MIC") (pin "1") (pinfunction "1_1") (pintype "passive"))
    )
    (net (code "20") (name "Net-(C13-Pad2)") (class "Default")
      (node (ref "C13") (pin "2") (pinfunction "2_2") (pintype "passive"))
      (node (ref "C14") (pin "1") (pinfunction "1_1") (pintype "passive"))
      (node (ref "R14") (pin "1") (pinfunction "1_1") (pintype "passive"))
    )
    (net (code "21") (name "Net-(C15-Pad2)") (class "Default")
      (node (ref "C15") (pin "2") (pinfunction "2_2") (pintype "passive"))
      (node (ref "R18") (pin "2") (pinfunction "2_2") (pintype "passive"))
      (node (ref "R19") (pin "1") (pinfunction "1_1") (pintype "passive"))
    )
    (net (code "22") (name "Net-(C17-Pad2)") (class "Default")
      (node (ref "C17") (pin "2") (pinfunction "2_2") (pintype "passive"))
      (node (ref "C18") (pin "1") (pinfunction "1_1") (pintype "passive"))
      (node (ref "R23") (pin "1") (pinfunction "1_1") (pintype "passive"))
    )
    (net (code "23") (name "Net-(C19-Pad2)") (class "Default")
      (node (ref "C19") (pin "2") (pinfunction "2_2") (pintype "passive"))
      (node (ref "R25") (pin "2") (pinfunction "2_2") (pintype "passive"))
      (node (ref "R26") (pin "1") (pinfunction "1_1") (pintype "passive"))
    )
    (net (code "24") (name "Net-(C21-Pad2)") (class "Default")
      (node (ref "C21") (pin "2") (pinfunction "2_2") (pintype "passive"))
      (node (ref "C22") (pin "1") (pinfunction "1_1") (pintype "passive"))
      (node (ref "R30") (pin "1") (pinfunction "1_1") (pintype "passive"))
    )
    (net (code "25") (name "Net-(C23-Pad2)") (class "Default")
      (node (ref "C23") (pin "2") (pinfunction "2_2") (pintype "passive"))
      (node (ref "R34") (pin "1") (pinfunction "1_1") (pintype "passive"))
      (node (ref "R35") (pin "1") (pinfunction "1_1") (pintype "passive"))
    )
    (net (code "26") (name "Net-(IC1A-+IN)") (class "Default")
      (node (ref "C9") (pin "2") (pinfunction "2_2") (pintype "passive"))
      (node (ref "IC1") (pin "3") (pinfunction "+IN_3") (pintype "input"))
      (node (ref "R39") (pin "2") (pinfunction "2_2") (pintype "passive"))
    )
    (net (code "27") (name "Net-(IC1A--IN)") (class "Default")
      (node (ref "IC1") (pin "2") (pinfunction "-IN_2") (pintype "input"))
      (node (ref "R29") (pin "2") (pinfunction "2_2") (pintype "passive"))
      (node (ref "R38") (pin "1") (pinfunction "1_1") (pintype "passive"))
    )
    (net (code "28") (name "Net-(IC1A-OUT)") (class "Default")
      (node (ref "C42") (pin "1") (pinfunction "1_1") (pintype "passive"))
      (node (ref "IC1") (pin "1") (pinfunction "OUT_1") (pintype "output"))
      (node (ref "R38") (pin "2") (pinfunction "2_2") (pintype "passive"))
    )
    (net (code "29") (name "Net-(IC2A-+IN)") (class "Default")
      (node (ref "C14") (pin "2") (pinfunction "2_2") (pintype "passive"))
      (node (ref "IC2") (pin "3") (pinfunction "+IN_3") (pintype "input"))
      (node (ref "R1") (pin "2") (pinfunction "2_2") (pintype "passive"))
    )
    (net (code "30") (name "Net-(IC2A--IN)") (class "Default")
      (node (ref "IC2") (pin "1") (pinfunction "OUT_1") (pintype "output"))
      (node (ref "IC2") (pin "2") (pinfunction "-IN_2") (pintype "input"))
      (node (ref "R14") (pin "2") (pinfunction "2_2") (pintype "passive"))
      (node (ref "R18") (pin "1") (pinfunction "1_1") (pintype "passive"))
    )
    (net (code "31") (name "Net-(IC2B-+IN)") (class "Default")
      (node (ref "C16") (pin "1") (pinfunction "1_1") (pintype "passive"))
      (node (ref "IC2") (pin "5") (pinfunction "+IN_5") (pintype "input"))
      (node (ref "R19") (pin "2") (pinfunction "2_2") (pintype "passive"))
    )
    (net (code "32") (name "Net-(IC2B--IN)") (class "Default")
      (node (ref "C15") (pin "1") (pinfunction "1_1") (pintype "passive"))
      (node (ref "IC2") (pin "6") (pinfunction "-IN_6") (pintype "input"))
      (node (ref "IC2") (pin "7") (pinfunction "OUT_7") (pintype "output"))
      (node (ref "POT_R_OPT") (pin "1") (pinfunction "1_1") (pintype "passive"))
    )
    (net (code "33") (name "Net-(IC3A-+IN)") (class "Default")
      (node (ref "C18") (pin "2") (pinfunction "2_2") (pintype "passive"))
      (node (ref "IC3") (pin "3") (pinfunction "+IN_3") (pintype "input"))
      (node (ref "R22") (pin "2") (pinfunction "2_2") (pintype "passive"))
    )
    (net (code "34") (name "Net-(IC3A--IN)") (class "Default")
      (node (ref "IC3") (pin "1") (pinfunction "OUT_1") (pintype "output"))
      (node (ref "IC3") (pin "2") (pinfunction "-IN_2") (pintype "input"))
      (node (ref "R23") (pin "2") (pinfunction "2_2") (pintype "passive"))
      (node (ref "R25") (pin "1") (pinfunction "1_1") (pintype "passive"))
    )
    (net (code "35") (name "Net-(IC3B-+IN)") (class "Default")
      (node (ref "C20") (pin "1") (pinfunction "1_1") (pintype "passive"))
      (node (ref "IC3") (pin "5") (pinfunction "+IN_5") (pintype "input"))
      (node (ref "R26") (pin "2") (pinfunction "2_2") (pintype "passive"))
    )
    (net (code "36") (name "Net-(IC3B--IN)") (class "Default")
      (node (ref "C19") (pin "1") (pinfunction "1_1") (pintype "passive"))
      (node (ref "IC3") (pin "6") (pinfunction "-IN_6") (pintype "input"))
      (node (ref "IC3") (pin "7") (pinfunction "OUT_7") (pintype "output"))
      (node (ref "POT_L_OPT") (pin "1") (pinfunction "1_1") (pintype "passive"))
    )
    (net (code "37") (name "Net-(IC4A-+IN)") (class "Default")
      (node (ref "C22") (pin "2") (pinfunction "2_2") (pintype "passive"))
      (node (ref "IC4") (pin "3") (pinfunction "+IN_3") (pintype "input"))
      (node (ref "R31") (pin "2") (pinfunction "2_2") (pintype "passive"))
    )
    (net (code "38") (name "Net-(IC4A--IN)") (class "Default")
      (node (ref "IC4") (pin "2") (pinfunction "-IN_2") (pintype "input"))
      (node (ref "P4") (pin "A") (pinfunction "A_A") (pintype "passive"))
      (node (ref "R33") (pin "2") (pinfunction "2_2") (pintype "passive"))
    )
    (net (code "39") (name "Net-(IC4A-OUT)") (class "Default")
      (node (ref "IC4") (pin "1") (pinfunction "OUT_1") (pintype "output"))
      (node (ref "R30") (pin "2") (pinfunction "2_2") (pintype "passive"))
      (node (ref "R32") (pin "2") (pinfunction "2_2") (pintype "passive"))
      (node (ref "R34") (pin "2") (pinfunction "2_2") (pintype "passive"))
    )
    (net (code "40") (name "Net-(IC4B-+IN)") (class "Default")
      (node (ref "C24") (pin "1") (pinfunction "1_1") (pintype "passive"))
      (node (ref "IC4") (pin "5") (pinfunction "+IN_5") (pintype "input"))
      (node (ref "R35") (pin "2") (pinfunction "2_2") (pintype "passive"))
    )
    (net (code "41") (name "Net-(IC5A--IN)") (class "Default")
      (node (ref "IC5") (pin "2") (pinfunction "-IN_2") (pintype "input"))
      (node (ref "R36") (pin "2") (pinfunction "2_2") (pintype "passive"))
      (node (ref "R37") (pin "1") (pinfunction "1_1") (pintype "passive"))
    )
    (net (code "42") (name "Net-(IC5A-OUT)") (class "Default")
      (node (ref "IC5") (pin "1") (pinfunction "OUT_1") (pintype "output"))
      (node (ref "POT_SUB_1_OPT") (pin "1") (pinfunction "1_1") (pintype "passive"))
      (node (ref "R37") (pin "2") (pinfunction "2_2") (pintype "passive"))
    )
    (net (code "43") (name "Net-(IC5B--IN)") (class "Default")
      (node (ref "IC5") (pin "6") (pinfunction "-IN_6") (pintype "input"))
      (node (ref "R4") (pin "2") (pinfunction "2_2") (pintype "passive"))
      (node (ref "R5") (pin "1") (pinfunction "1_1") (pintype "passive"))
    )
    (net (code "44") (name "Net-(IC6A--IN)") (class "Default")
      (node (ref "IC6") (pin "2") (pinfunction "-IN_2") (pintype "input"))
      (node (ref "R42") (pin "2") (pinfunction "2_2") (pintype "passive"))
      (node (ref "R43") (pin "1") (pinfunction "1_1") (pintype "passive"))
    )
    (net (code "45") (name "Net-(IC6B--IN)") (class "Default")
      (node (ref "IC6") (pin "6") (pinfunction "-IN_6") (pintype "input"))
      (node (ref "R2") (pin "2") (pinfunction "2_2") (pintype "passive"))
      (node (ref "R3") (pin "1") (pinfunction "1_1") (pintype "passive"))
    )
    (net (code "46") (name "Net-(IN1A-KL)") (class "Default")
      (node (ref "IN1") (pin "P$1") (pinfunction "KL_P$1") (pintype "passive"))
      (node (ref "SW1") (pin "1") (pinfunction "S0B_1") (pintype "bidirectional"))
    )
    (net (code "47") (name "Net-(IN1C-KL)") (class "Default")
      (node (ref "IN1") (pin "P$3") (pinfunction "KL_P$3") (pintype "passive"))
      (node (ref "SW1") (pin "12") (pinfunction "S0A_12") (pintype "bidirectional"))
    )
    (net (code "48") (name "Net-(IN2A-KL)") (class "Default")
      (node (ref "IN2") (pin "P$1") (pinfunction "KL_P$1") (pintype "passive"))
      (node (ref "SW1") (pin "5") (pinfunction "S1B_5") (pintype "bidirectional"))
    )
    (net (code "49") (name "Net-(IN2C-KL)") (class "Default")
      (node (ref "IN2") (pin "P$3") (pinfunction "KL_P$3") (pintype "passive"))
      (node (ref "SW1") (pin "14") (pinfunction "S1A_14") (pintype "bidirectional"))
    )
    (net (code "50") (name "Net-(IN3A-KL)") (class "Default")
      (node (ref "IN3") (pin "P$1") (pinfunction "KL_P$1") (pintype "passive"))
      (node (ref "SW1") (pin "2") (pinfunction "S2B_2") (pintype "bidirectional"))
    )
    (net (code "51") (name "Net-(IN3C-KL)") (class "Default")
      (node (ref "IN3") (pin "P$3") (pinfunction "KL_P$3") (pintype "passive"))
      (node (ref "SW1") (pin "15") (pinfunction "S2A_15") (pintype "bidirectional"))
    )
    (net (code "52") (name "Net-(IN4A-KL)") (class "Default")
      (node (ref "IN4") (pin "P$1") (pinfunction "KL_P$1") (pintype "passive"))
      (node (ref "SW1") (pin "4") (pinfunction "S3B_4") (pintype "bidirectional"))
    )
    (net (code "53") (name "Net-(IN4C-KL)") (class "Default")
      (node (ref "IN4") (pin "P$3") (pinfunction "KL_P$3") (pintype "passive"))
      (node (ref "SW1") (pin "11") (pinfunction "S3A_11") (pintype "bidirectional"))
    )
    (net (code "54") (name "Net-(IN5A-KL)") (class "Default")
      (node (ref "IN5") (pin "P$1") (pinfunction "KL_P$1") (pintype "passive"))
      (node (ref "SW2") (pin "5") (pinfunction "S1B_5") (pintype "bidirectional"))
    )
    (net (code "55") (name "Net-(IN5C-KL)") (class "Default")
      (node (ref "IN5") (pin "P$3") (pinfunction "KL_P$3") (pintype "passive"))
      (node (ref "SW2") (pin "14") (pinfunction "S1A_14") (pintype "bidirectional"))
    )
    (net (code "56") (name "Net-(IN6A-KL)") (class "Default")
      (node (ref "IN6") (pin "P$1") (pinfunction "KL_P$1") (pintype "passive"))
      (node (ref "SW2") (pin "2") (pinfunction "S2B_2") (pintype "bidirectional"))
    )
    (net (code "57") (name "Net-(IN6C-KL)") (class "Default")
      (node (ref "IN6") (pin "P$3") (pinfunction "KL_P$3") (pintype "passive"))
      (node (ref "SW2") (pin "15") (pinfunction "S2A_15") (pintype "bidirectional"))
    )
    (net (code "58") (name "Net-(IN7A-KL)") (class "Default")
      (node (ref "IN7") (pin "P$1") (pinfunction "KL_P$1") (pintype "passive"))
      (node (ref "SW2") (pin "4") (pinfunction "S3B_4") (pintype "bidirectional"))
    )
    (net (code "59") (name "Net-(IN7C-KL)") (class "Default")
      (node (ref "IN7") (pin "P$3") (pinfunction "KL_P$3") (pintype "passive"))
      (node (ref "SW2") (pin "11") (pinfunction "S3A_11") (pintype "bidirectional"))
    )
    (net (code "60") (name "Net-(P4-PadE)") (class "Default")
      (node (ref "P4") (pin "E") (pinfunction "E_E") (pintype "passive"))
      (node (ref "P4") (pin "S") (pinfunction "S_S") (pintype "passive"))
      (node (ref "R32") (pin "1") (pinfunction "1_1") (pintype "passive"))
    )
    (net (code "61") (name "Net-(POT1-SCK)") (class "Default")
      (node (ref "POT1") (pin "2") (pinfunction "SCK_2") (pintype "bidirectional"))
      (node (ref "POT2") (pin "2") (pinfunction "SCK_2") (pintype "bidirectional"))
      (node (ref "SPI_CLK") (pin "6") (pinfunction "6_6") (pintype "passive"))
    )
    (net (code "62") (name "Net-(POT1-SI)") (class "Default")
      (node (ref "POT1") (pin "3") (pinfunction "SI_3") (pintype "bidirectional"))
      (node (ref "SPI_CLK") (pin "2") (pinfunction "2_2") (pintype "passive"))
    )
    (net (code "63") (name "Net-(POT1-SO)") (class "Default")
      (node (ref "POT1") (pin "13") (pinfunction "SO_13") (pintype "bidirectional"))
      (node (ref "SPI_CLK") (pin "4") (pinfunction "4_4") (pintype "passive"))
    )
    (net (code "64") (name "Net-(POT1-~{CS})") (class "Default")
      (node (ref "CS") (pin "1") (pinfunction "1_1") (pintype "passive"))
      (node (ref "POT1") (pin "1") (pinfunction "~{CS}_1") (pintype "bidirectional"))
    )
    (net (code "65") (name "Net-(POT2-PA1)") (class "Default")
      (node (ref "C42") (pin "2") (pinfunction "2_2") (pintype "passive"))
      (node (ref "POT2") (pin "7") (pinfunction "PA1_7") (pintype "bidirectional"))
      (node (ref "R16") (pin "1") (pinfunction "1_1") (pintype "passive"))
      (node (ref "R17") (pin "2") (pinfunction "2_2") (pintype "passive"))
    )
    (net (code "66") (name "Net-(POT2-PW1)") (class "Default")
      (node (ref "C4") (pin "1") (pinfunction "1_1") (pintype "passive"))
      (node (ref "POT2") (pin "6") (pinfunction "PW1_6") (pintype "bidirectional"))
    )
    (net (code "67") (name "Net-(POT2-SI)") (class "Default")
      (node (ref "POT2") (pin "3") (pinfunction "SI_3") (pintype "bidirectional"))
      (node (ref "SPI_CLK") (pin "3") (pinfunction "3_3") (pintype "passive"))
    )
    (net (code "68") (name "Net-(POT2-SO)") (class "Default")
      (node (ref "POT2") (pin "13") (pinfunction "SO_13") (pintype "bidirectional"))
      (node (ref "SPI_CLK") (pin "1") (pinfunction "1_1") (pintype "passive"))
    )
    (net (code "69") (name "Net-(POT2-~{CS})") (class "Default")
      (node (ref "CS") (pin "2") (pinfunction "2_2") (pintype "passive"))
      (node (ref "POT2") (pin "1") (pinfunction "~{CS}_1") (pintype "bidirectional"))
    )
    (net (code "70") (name "Net-(SW1-A0)") (class "Default")
      (node (ref "BIN1") (pin "1") (pinfunction "1_1") (pintype "passive"))
      (node (ref "SW1") (pin "10") (pinfunction "A0_10") (pintype "input"))
    )
    (net (code "71") (name "Net-(SW1-A1)") (class "Default")
      (node (ref "BIN1") (pin "2") (pinfunction "2_2") (pintype "passive"))
      (node (ref "SW1") (pin "9") (pinfunction "A1_9") (pintype "input"))
    )
    (net (code "72") (name "Net-(SW2-A0)") (class "Default")
      (node (ref "BIN2") (pin "1") (pinfunction "1_1") (pintype "passive"))
      (node (ref "SW2") (pin "10") (pinfunction "A0_10") (pintype "input"))
    )
    (net (code "73") (name "Net-(SW2-A1)") (class "Default")
      (node (ref "BIN2") (pin "2") (pinfunction "2_2") (pintype "passive"))
      (node (ref "SW2") (pin "9") (pinfunction "A1_9") (pintype "input"))
    )
    (net (code "74") (name "R1") (class "Default")
      (node (ref "SW1") (pin "13") (pinfunction "DA_13") (pintype "bidirectional"))
      (node (ref "SW2") (pin "12") (pinfunction "S0A_12") (pintype "bidirectional"))
    )
    (net (code "75") (name "R2") (class "Default")
      (node (ref "C5") (pin "1") (pinfunction "1_1") (pintype "passive"))
      (node (ref "R20") (pin "1") (pinfunction "1_1") (pintype "passive"))
      (node (ref "R27") (pin "2") (pinfunction "2_2") (pintype "passive"))
      (node (ref "SW2") (pin "13") (pinfunction "DA_13") (pintype "bidirectional"))
    )
    (net (code "76") (name "R3") (class "Default")
      (node (ref "C5") (pin "2") (pinfunction "2_2") (pintype "passive"))
      (node (ref "POT1") (pin "8") (pinfunction "PA0_8") (pintype "bidirectional"))
      (node (ref "R7") (pin "1") (pinfunction "1_1") (pintype "passive"))
      (node (ref "R9") (pin "2") (pinfunction "2_2") (pintype "passive"))
    )
    (net (code "77") (name "R4") (class "Default")
      (node (ref "C7") (pin "1") (pinfunction "1_1") (pintype "passive"))
      (node (ref "POT1") (pin "9") (pinfunction "PW0_9") (pintype "bidirectional"))
    )
    (net (code "78") (name "R5") (class "Default")
      (node (ref "C7") (pin "2") (pinfunction "2_2") (pintype "passive"))
      (node (ref "IC5") (pin "5") (pinfunction "+IN_5") (pintype "input"))
      (node (ref "R10") (pin "2") (pinfunction "2_2") (pintype "passive"))
    )
    (net (code "79") (name "R6") (class "Default")
      (node (ref "IC5") (pin "7") (pinfunction "OUT_7") (pintype "output"))
      (node (ref "R5") (pin "2") (pinfunction "2_2") (pintype "passive"))
      (node (ref "R_FILTER_JPR") (pin "2") (pinfunction "2_2") (pintype "passive"))
    )
    (net (code "80") (name "R_IN") (class "Default")
      (node (ref "C17") (pin "1") (pinfunction "1_1") (pintype "passive"))
      (node (ref "R_FILTER_JPR") (pin "3") (pinfunction "3_3") (pintype "passive"))
    )
    (net (code "81") (name "R_OUT") (class "Default")
      (node (ref "OUTPUT") (pin "8") (pinfunction "8_8") (pintype "passive"))
      (node (ref "POT_R_OPT") (pin "2") (pinfunction "2_2") (pintype "passive"))
      (node (ref "R_FILTER_JPR") (pin "1") (pinfunction "1_1") (pintype "passive"))
    )
    (net (code "82") (name "SUB1") (class "Default")
      (node (ref "IC1") (pin "6") (pinfunction "-IN_6") (pintype "input"))
      (node (ref "R11") (pin "2") (pinfunction "2_2") (pintype "passive"))
      (node (ref "R27") (pin "1") (pinfunction "1_1") (pintype "passive"))
      (node (ref "R28") (pin "1") (pinfunction "1_1") (pintype "passive"))
    )
    (net (code "83") (name "SUB2") (class "Default")
      (node (ref "ADD") (pin "2") (pinfunction "2_2") (pintype "passive"))
      (node (ref "IC1") (pin "7") (pinfunction "OUT_7") (pintype "output"))
      (node (ref "R11") (pin "1") (pinfunction "1_1") (pintype "passive"))
    )
    (net (code "84") (name "SUB3") (class "Default")
      (node (ref "C43") (pin "2") (pinfunction "2_2") (pintype "passive"))
      (node (ref "POT2") (pin "8") (pinfunction "PA0_8") (pintype "bidirectional"))
      (node (ref "R12") (pin "1") (pinfunction "1_1") (pintype "passive"))
      (node (ref "R13") (pin "2") (pinfunction "2_2") (pintype "passive"))
    )
    (net (code "85") (name "SUB4") (class "Default")
      (node (ref "C11") (pin "1") (pinfunction "1_1") (pintype "passive"))
      (node (ref "POT2") (pin "9") (pinfunction "PW0_9") (pintype "bidirectional"))
    )
    (net (code "86") (name "SUB5") (class "Default")
      (node (ref "C11") (pin "2") (pinfunction "2_2") (pintype "passive"))
      (node (ref "IC6") (pin "5") (pinfunction "+IN_5") (pintype "input"))
      (node (ref "R15") (pin "2") (pinfunction "2_2") (pintype "passive"))
    )
    (net (code "87") (name "SUB_IN") (class "Default")
      (node (ref "C21") (pin "1") (pinfunction "1_1") (pintype "passive"))
      (node (ref "IC6") (pin "7") (pinfunction "OUT_7") (pintype "output"))
      (node (ref "R3") (pin "2") (pinfunction "2_2") (pintype "passive"))
    )
    (net (code "88") (name "SUB_PHASE") (class "Default")
      (node (ref "C23") (pin "1") (pinfunction "1_1") (pintype "passive"))
      (node (ref "IC4") (pin "6") (pinfunction "-IN_6") (pintype "input"))
      (node (ref "IC4") (pin "7") (pinfunction "OUT_7") (pintype "output"))
      (node (ref "POT_SUB_2_OPT") (pin "1") (pinfunction "1_1") (pintype "passive"))
      (node (ref "R36") (pin "1") (pinfunction "1_1") (pintype "passive"))
    )
  )
)
